# mc_spine_con.net
KiCad netlist of a schematic drawn in EAGLE
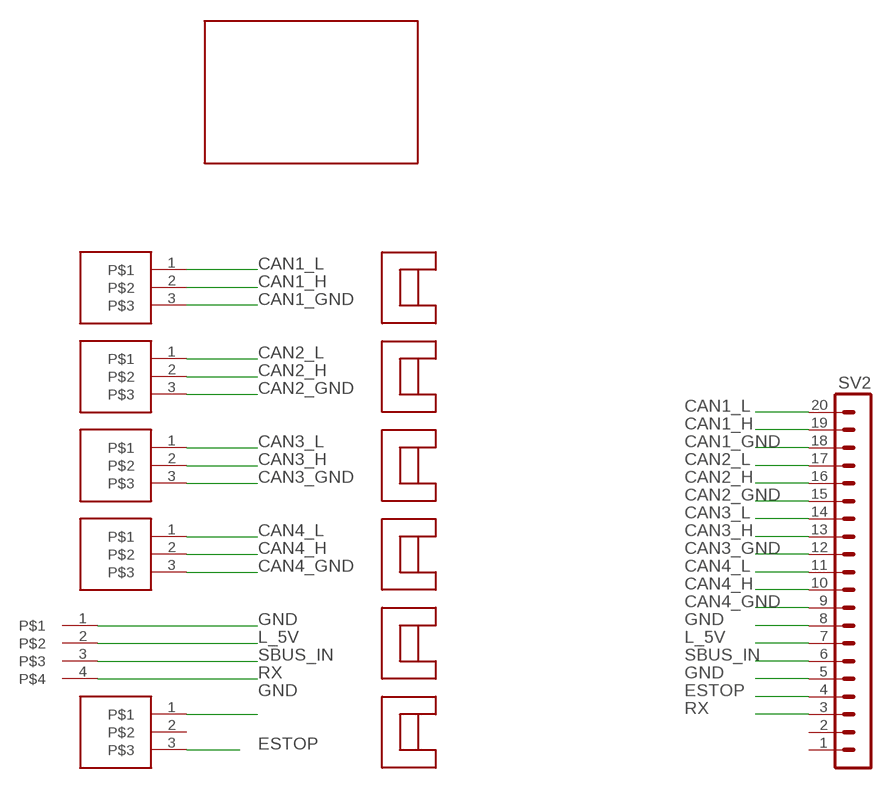
[diagram p0: schematic, sheet 1]

(export (version "E")
  (design (tool "Eeschema 10.0.6"))
  (components
    (comp (ref "SV2")
      (value "MA20-1L")
      (footprint "eagle-import:MA20-1L")
      (libsource (lib "eagle-import") (part "MA20-1L"))
    )
    (comp (ref "U$1")
      (value "3-PIN")
      (footprint "eagle-import:M80-8430342")
      (libsource (lib "eagle-import") (part "3-PIN"))
    )
    (comp (ref "U$2")
      (value "UP_BOARD_NOPINS")
      (footprint "eagle-import:UP_BOARD_NOPINS")
      (libsource (lib "eagle-import") (part "UP_BOARD_NOPINS"))
    )
    (comp (ref "U$3")
      (value "3-PIN")
      (footprint "eagle-import:M80-8430342")
      (libsource (lib "eagle-import") (part "3-PIN"))
    )
    (comp (ref "U$4")
      (value "3-PIN")
      (footprint "eagle-import:M80-8430342")
      (libsource (lib "eagle-import") (part "3-PIN"))
    )
    (comp (ref "U$5")
      (value "4-PIN")
      (footprint "eagle-import:M80-8430442")
      (libsource (lib "eagle-import") (part "4-PIN"))
    )
    (comp (ref "U$6")
      (value "3-PIN")
      (footprint "eagle-import:M80-8430342")
      (libsource (lib "eagle-import") (part "3-PIN"))
    )
    (comp (ref "U$7")
      (value "SMD_CABLE_CLIPSS8111-46R")
      (footprint "eagle-import:S8111-46R")
      (libsource (lib "eagle-import") (part "SMD_CABLE_CLIPSS8111-46R"))
    )
    (comp (ref "U$8")
      (value "SMD_CABLE_CLIPSS8111-46R")
      (footprint "eagle-import:S8111-46R")
      (libsource (lib "eagle-import") (part "SMD_CABLE_CLIPSS8111-46R"))
    )
    (comp (ref "U$9")
      (value "SMD_CABLE_CLIPSS8111-46R")
      (footprint "eagle-import:S8111-46R")
      (libsource (lib "eagle-import") (part "SMD_CABLE_CLIPSS8111-46R"))
    )
    (comp (ref "U$10")
      (value "SMD_CABLE_CLIPSS8111-46R")
      (footprint "eagle-import:S8111-46R")
      (libsource (lib "eagle-import") (part "SMD_CABLE_CLIPSS8111-46R"))
    )
    (comp (ref "U$11")
      (value "SMD_CABLE_CLIPSS8111-46R")
      (footprint "eagle-import:S8111-46R")
      (libsource (lib "eagle-import") (part "SMD_CABLE_CLIPSS8111-46R"))
    )
    (comp (ref "U$12")
      (value "3-PIN")
      (footprint "eagle-import:M80-8430342")
      (libsource (lib "eagle-import") (part "3-PIN"))
    )
    (comp (ref "U$13")
      (value "SMD_CABLE_CLIPSS8111-46R")
      (footprint "eagle-import:S8111-46R")
      (libsource (lib "eagle-import") (part "SMD_CABLE_CLIPSS8111-46R"))
    )
  )
  (nets
    (net (code "1") (name "/CAN1_GND") (class "Default")
      (node (ref "SV2") (pin "18") (pinfunction "18_18") (pintype "passive"))
      (node (ref "U$12") (pin "3") (pinfunction "P$3_3") (pintype "bidirectional"))
    )
    (net (code "2") (name "/CAN1_H") (class "Default")
      (node (ref "SV2") (pin "19") (pinfunction "19_19") (pintype "passive"))
      (node (ref "U$12") (pin "2") (pinfunction "P$2_2") (pintype "bidirectional"))
    )
    (net (code "3") (name "/CAN1_L") (class "Default")
      (node (ref "SV2") (pin "20") (pinfunction "20_20") (pintype "passive"))
      (node (ref "U$12") (pin "1") (pinfunction "P$1_1") (pintype "bidirectional"))
    )
    (net (code "4") (name "/CAN2_GND") (class "Default")
      (node (ref "SV2") (pin "15") (pinfunction "15_15") (pintype "passive"))
      (node (ref "U$1") (pin "3") (pinfunction "P$3_3") (pintype "bidirectional"))
    )
    (net (code "5") (name "/CAN2_H") (class "Default")
      (node (ref "SV2") (pin "16") (pinfunction "16_16") (pintype "passive"))
      (node (ref "U$1") (pin "2") (pinfunction "P$2_2") (pintype "bidirectional"))
    )
    (net (code "6") (name "/CAN2_L") (class "Default")
      (node (ref "SV2") (pin "17") (pinfunction "17_17") (pintype "passive"))
      (node (ref "U$1") (pin "1") (pinfunction "P$1_1") (pintype "bidirectional"))
    )
    (net (code "7") (name "/CAN3_GND") (class "Default")
      (node (ref "SV2") (pin "12") (pinfunction "12_12") (pintype "passive"))
      (node (ref "U$3") (pin "3") (pinfunction "P$3_3") (pintype "bidirectional"))
    )
    (net (code "8") (name "/CAN3_H") (class "Default")
      (node (ref "SV2") (pin "13") (pinfunction "13_13") (pintype "passive"))
      (node (ref "U$3") (pin "2") (pinfunction "P$2_2") (pintype "bidirectional"))
    )
    (net (code "9") (name "/CAN3_L") (class "Default")
      (node (ref "SV2") (pin "14") (pinfunction "14_14") (pintype "passive"))
      (node (ref "U$3") (pin "1") (pinfunction "P$1_1") (pintype "bidirectional"))
    )
    (net (code "10") (name "/CAN4_GND") (class "Default")
      (node (ref "SV2") (pin "9") (pinfunction "9_9") (pintype "passive"))
      (node (ref "U$4") (pin "3") (pinfunction "P$3_3") (pintype "bidirectional"))
    )
    (net (code "11") (name "/CAN4_H") (class "Default")
      (node (ref "SV2") (pin "10") (pinfunction "10_10") (pintype "passive"))
      (node (ref "U$4") (pin "2") (pinfunction "P$2_2") (pintype "bidirectional"))
    )
    (net (code "12") (name "/CAN4_L") (class "Default")
      (node (ref "SV2") (pin "11") (pinfunction "11_11") (pintype "passive"))
      (node (ref "U$4") (pin "1") (pinfunction "P$1_1") (pintype "bidirectional"))
    )
    (net (code "13") (name "/ESTOP") (class "Default")
      (node (ref "SV2") (pin "4") (pinfunction "4_4") (pintype "passive"))
      (node (ref "U$6") (pin "3") (pinfunction "P$3_3") (pintype "bidirectional"))
    )
    (net (code "14") (name "/GND") (class "Default")
      (node (ref "SV2") (pin "5") (pinfunction "5_5") (pintype "passive"))
      (node (ref "SV2") (pin "8") (pinfunction "8_8") (pintype "passive"))
      (node (ref "U$5") (pin "1") (pinfunction "P$1_1") (pintype "bidirectional"))
      (node (ref "U$6") (pin "1") (pinfunction "P$1_1") (pintype "bidirectional"))
    )
    (net (code "15") (name "/L_5V") (class "Default")
      (node (ref "SV2") (pin "7") (pinfunction "7_7") (pintype "passive"))
      (node (ref "U$5") (pin "2") (pinfunction "P$2_2") (pintype "bidirectional"))
    )
    (net (code "16") (name "/RX") (class "Default")
      (node (ref "SV2") (pin "3") (pinfunction "3_3") (pintype "passive"))
      (node (ref "U$5") (pin "4") (pinfunction "P$4_4") (pintype "bidirectional"))
    )
    (net (code "17") (name "/SBUS_IN") (class "Default")
      (node (ref "SV2") (pin "6") (pinfunction "6_6") (pintype "passive"))
      (node (ref "U$5") (pin "3") (pinfunction "P$3_3") (pintype "bidirectional"))
    )
    (net (code "18") (name "unconnected-(SV2-Pad1)") (class "Default")
      (node (ref "SV2") (pin "1") (pinfunction "1_1") (pintype "passive"))
    )
    (net (code "19") (name "unconnected-(SV2-Pad2)") (class "Default")
      (node (ref "SV2") (pin "2") (pinfunction "2_2") (pintype "passive"))
    )
    (net (code "20") (name "unconnected-(U$6-P$2-Pad2)") (class "Default")
      (node (ref "U$6") (pin "2") (pinfunction "P$2_2") (pintype "bidirectional"))
    )
  )
)
